# SCH_Plantcare_Module-v3_2024-10-30.net
KiCad netlist of a schematic drawn in EasyEDA
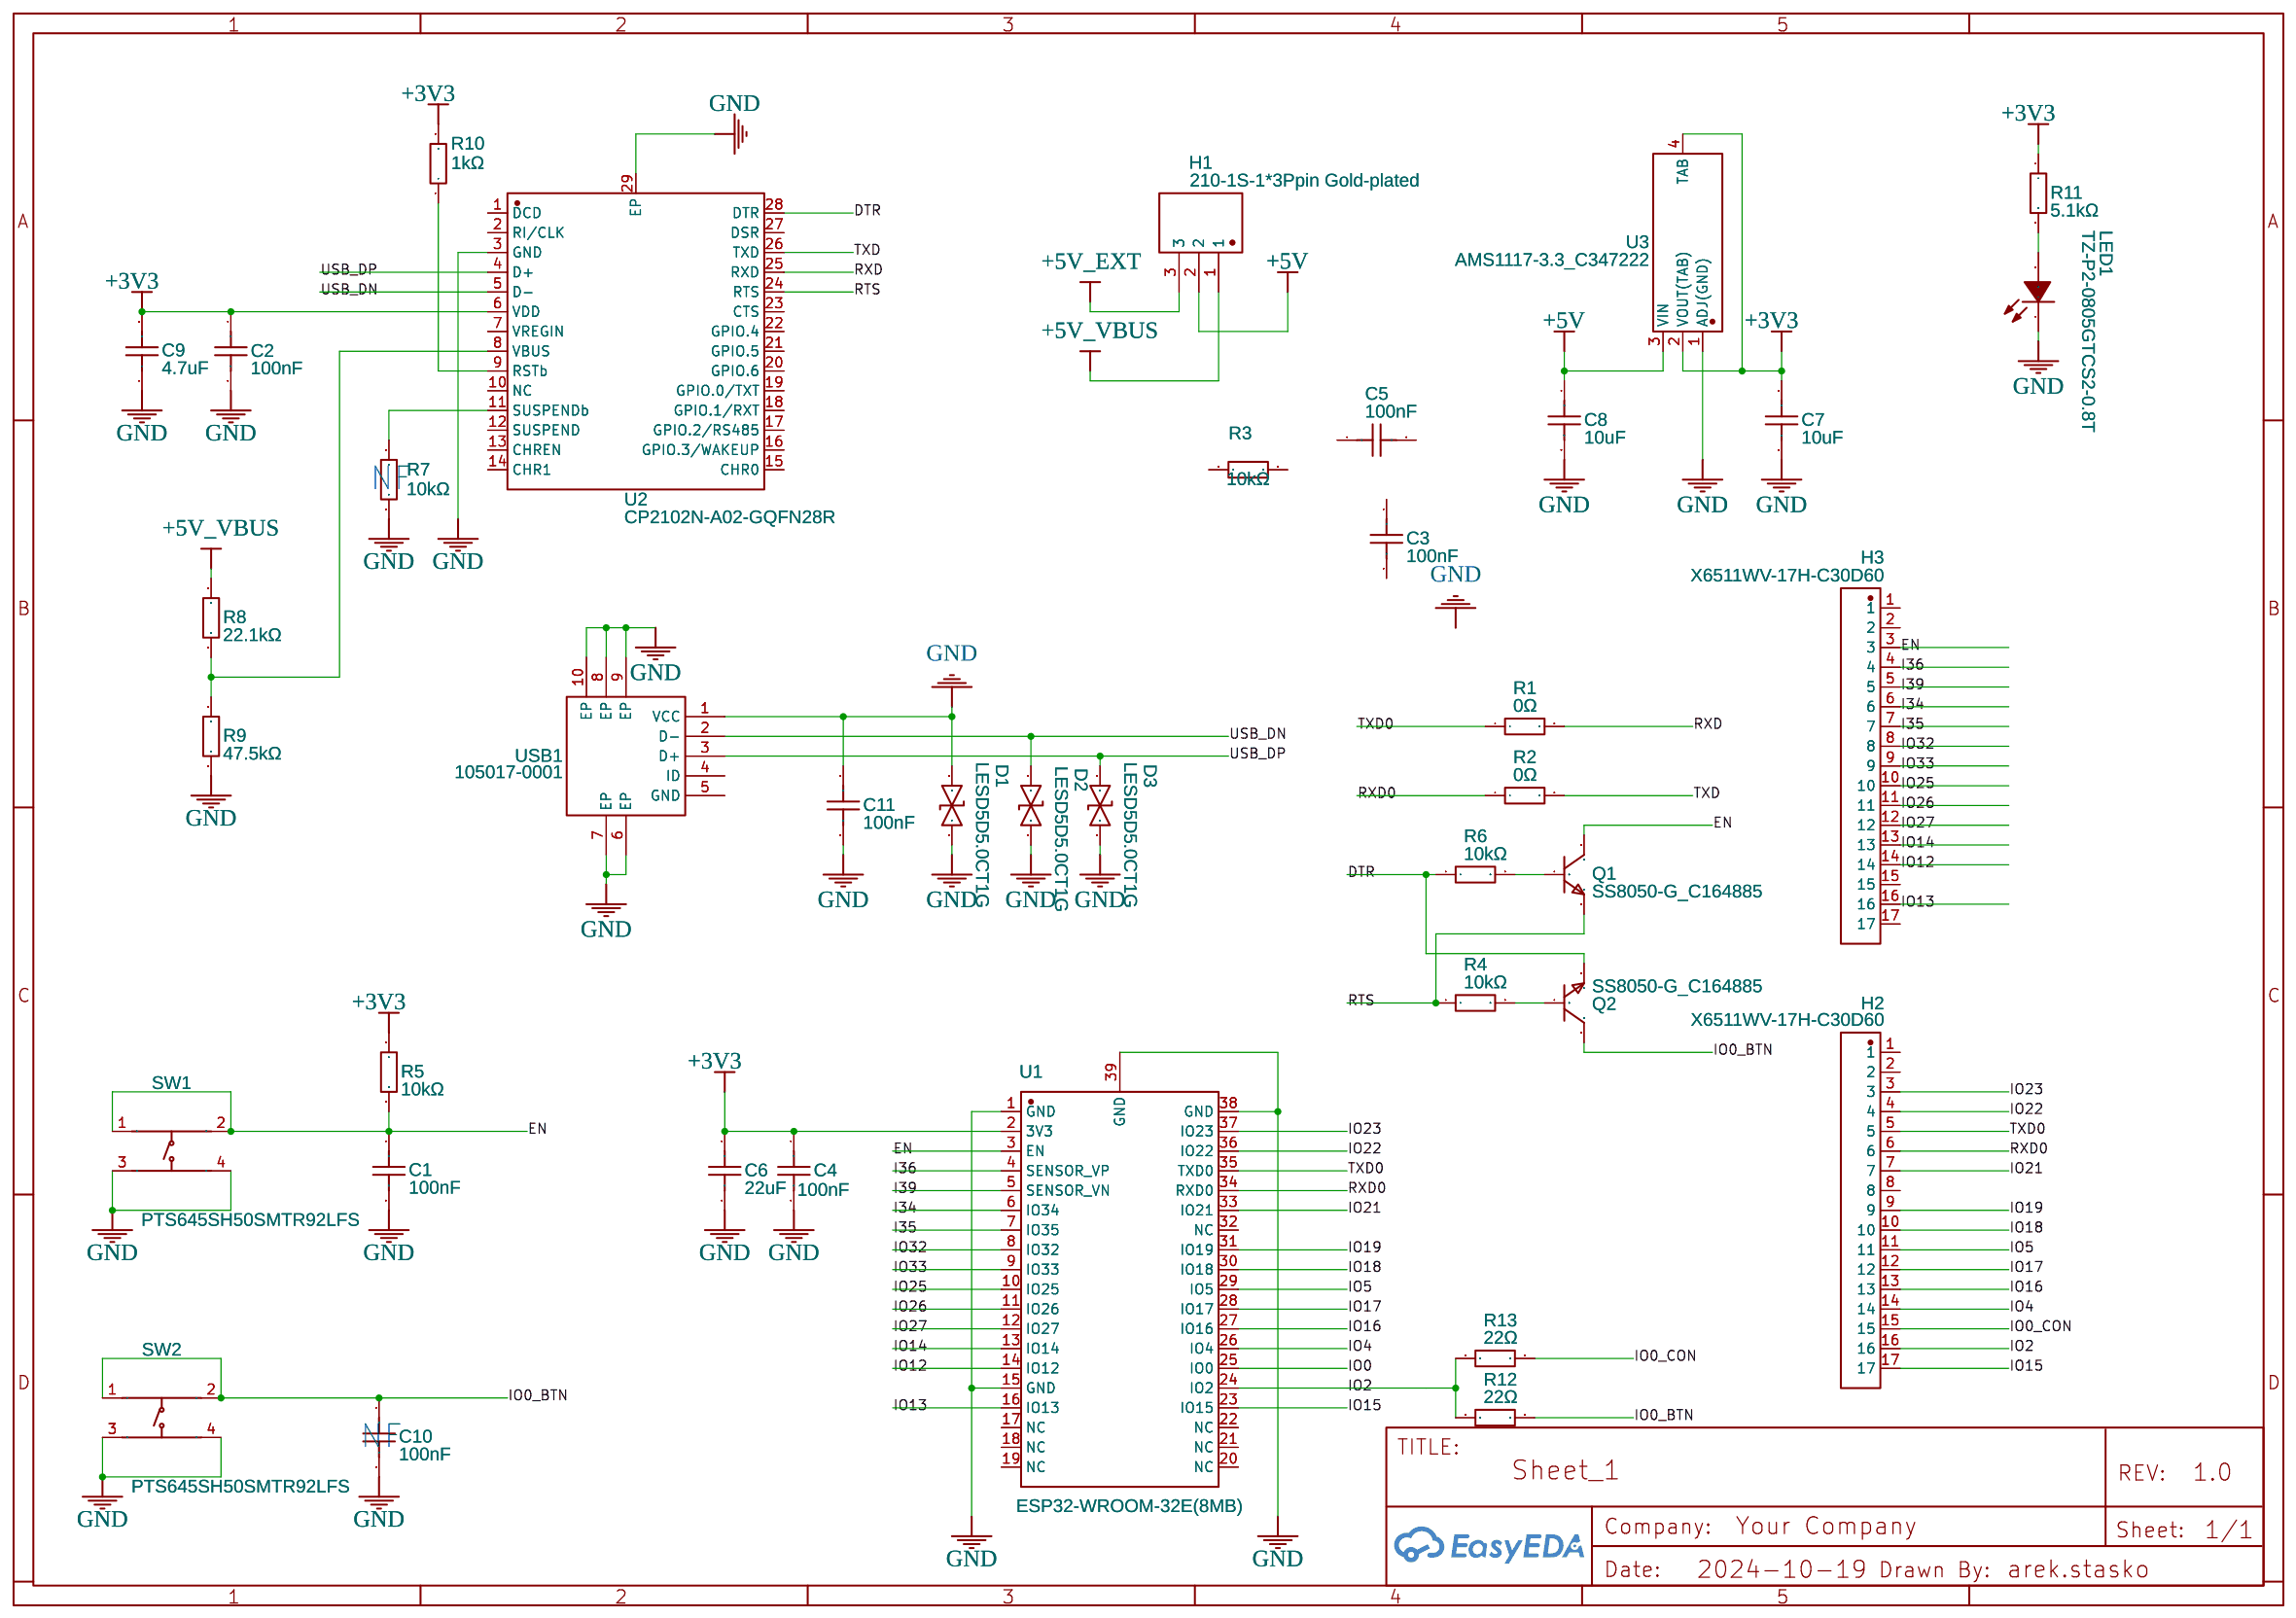
[diagram p0: schematic sheet]

(export (version "E")
  (design (tool "Eeschema 10.0.6"))
  (components
    (comp (ref "C1")
      (value "100nF")
      (fields
        (field (name "Manufacturer Part") "CL05B104KO5NNNC")
        (field (name "Manufacturer") "SAMSUNG(三星)")
      )
      (libsource (lib "") (part "CL05B104KO5NNNC_1"))
    )
    (comp (ref "C2")
      (value "100nF")
      (fields
        (field (name "Manufacturer Part") "CL05B104KO5NNNC")
        (field (name "Manufacturer") "SAMSUNG(三星)")
      )
      (libsource (lib "") (part "CL05B104KO5NNNC_1"))
    )
    (comp (ref "C3")
      (value "100nF")
      (fields
        (field (name "Manufacturer Part") "CL05B104KO5NNNC")
        (field (name "Manufacturer") "SAMSUNG(三星)")
      )
      (libsource (lib "") (part "CL05B104KO5NNNC_1"))
    )
    (comp (ref "C4")
      (value "100nF")
      (fields
        (field (name "Manufacturer Part") "CL05B104KO5NNNC")
        (field (name "Manufacturer") "SAMSUNG(三星)")
      )
      (libsource (lib "") (part "CL05B104KO5NNNC_1"))
    )
    (comp (ref "C5")
      (value "100nF")
      (fields
        (field (name "Manufacturer Part") "CL05B104KO5NNNC")
        (field (name "Manufacturer") "SAMSUNG(三星)")
      )
      (libsource (lib "") (part "CL05B104KO5NNNC"))
    )
    (comp (ref "C6")
      (value "22uF")
      (fields
        (field (name "Manufacturer Part") "CL21A226MAYNNNE")
        (field (name "Manufacturer") "SAMSUNG(三星)")
      )
      (libsource (lib "") (part "CL21A226MAYNNNE"))
    )
    (comp (ref "C7")
      (value "10uF")
      (fields
        (field (name "Manufacturer Part") "CL05A106MP5NUNC")
        (field (name "Manufacturer") "SAMSUNG(三星)")
      )
      (libsource (lib "") (part "CL05A106MP5NUNC_C315248"))
    )
    (comp (ref "C8")
      (value "10uF")
      (fields
        (field (name "Manufacturer Part") "CL05A106MP5NUNC")
        (field (name "Manufacturer") "SAMSUNG(三星)")
      )
      (libsource (lib "") (part "CL05A106MP5NUNC_C315248"))
    )
    (comp (ref "C9")
      (value "4.7uF")
      (fields
        (field (name "Manufacturer Part") "CL05A475KP5NRNC")
        (field (name "Manufacturer") "SAMSUNG(三星)")
      )
      (libsource (lib "") (part "CL05A475KP5NRNC"))
    )
    (comp (ref "C10")
      (value "100nF")
      (fields
        (field (name "Manufacturer Part") "CL05B104KO5NNNC")
        (field (name "Manufacturer") "SAMSUNG(三星)")
      )
      (libsource (lib "") (part "CL05B104KO5NNNC_1"))
    )
    (comp (ref "C11")
      (value "100nF")
      (fields
        (field (name "Manufacturer Part") "CL05B104KO5NNNC")
        (field (name "Manufacturer") "SAMSUNG(三星)")
      )
      (libsource (lib "") (part "CL05B104KO5NNNC_1"))
    )
    (comp (ref "D1")
      (value "LESD5D5.0CT1G")
      (fields (field (name "Manufacturer") "LRC(乐山无线电)"))
      (libsource (lib "") (part "LESD5D5.0CT1G_1"))
    )
    (comp (ref "D2")
      (value "LESD5D5.0CT1G")
      (fields (field (name "Manufacturer") "LRC(乐山无线电)"))
      (libsource (lib "") (part "LESD5D5.0CT1G"))
    )
    (comp (ref "D3")
      (value "LESD5D5.0CT1G")
      (fields (field (name "Manufacturer") "LRC(乐山无线电)"))
      (libsource (lib "") (part "LESD5D5.0CT1G"))
    )
    (comp (ref "H1")
      (value "210-1S-1*3Ppin Gold-plated")
      (fields (field (name "Manufacturer Part") "B-2101S03P-A110") (field (name "Manufacturer") "Ckmtw(灿科盟)"))
      (libsource (lib "") (part "210-1S-1*3Ppin Gold-plated"))
    )
    (comp (ref "H2")
      (value "X6511WV-17H-C30D60")
      (fields
        (field (name "Manufacturer Part") "X6511WV-17H-C60D30")
        (field (name "Manufacturer") "XKB Connection(中国星坤)")
      )
      (libsource (lib "") (part "X6511WV-17H-C30D60"))
    )
    (comp (ref "H3")
      (value "X6511WV-17H-C30D60")
      (fields
        (field (name "Manufacturer Part") "X6511WV-17H-C60D30")
        (field (name "Manufacturer") "XKB Connection(中国星坤)")
      )
      (libsource (lib "") (part "X6511WV-17H-C30D60"))
    )
    (comp (ref "LED1")
      (value "TZ-P2-0805GTCS2-0.8T")
      (fields (field (name "Manufacturer") "TUOZHAN(拓展光电)"))
      (libsource (lib "") (part "TZ-P2-0805GTCS2-0.8T"))
    )
    (comp (ref "Q1")
      (value "SS8050-G_C164885")
      (fields (field (name "Manufacturer Part") "SS8050-G") (field (name "Manufacturer") "CJ(江苏长电/长晶)"))
      (libsource (lib "") (part "SS8050-G_C164885"))
    )
    (comp (ref "Q2")
      (value "SS8050-G_C164885")
      (fields (field (name "Manufacturer Part") "SS8050-G") (field (name "Manufacturer") "CJ(江苏长电/长晶)"))
      (libsource (lib "") (part "SS8050-G_C164885_1"))
    )
    (comp (ref "R1")
      (value "0Ω")
      (fields
        (field (name "Manufacturer Part") "0402WGF0000TCE")
        (field (name "Manufacturer") "UNI-ROYAL(厚声)")
      )
      (libsource (lib "") (part "0402WGF0000TCE"))
    )
    (comp (ref "R2")
      (value "0Ω")
      (fields
        (field (name "Manufacturer Part") "0402WGF0000TCE")
        (field (name "Manufacturer") "UNI-ROYAL(厚声)")
      )
      (libsource (lib "") (part "0402WGF0000TCE"))
    )
    (comp (ref "R3")
      (value "10kΩ")
      (fields
        (field (name "Manufacturer Part") "0402WGF1002TCE")
        (field (name "Manufacturer") "UNI-ROYAL(厚声)")
      )
      (libsource (lib "") (part "0402WGF1002TCE_1"))
    )
    (comp (ref "R4")
      (value "10kΩ")
      (fields
        (field (name "Manufacturer Part") "0402WGF1002TCE")
        (field (name "Manufacturer") "UNI-ROYAL(厚声)")
      )
      (libsource (lib "") (part "0402WGF1002TCE_1"))
    )
    (comp (ref "R5")
      (value "10kΩ")
      (fields
        (field (name "Manufacturer Part") "0402WGF1002TCE")
        (field (name "Manufacturer") "UNI-ROYAL(厚声)")
      )
      (libsource (lib "") (part "0402WGF1002TCE"))
    )
    (comp (ref "R6")
      (value "10kΩ")
      (fields
        (field (name "Manufacturer Part") "0402WGF1002TCE")
        (field (name "Manufacturer") "UNI-ROYAL(厚声)")
      )
      (libsource (lib "") (part "0402WGF1002TCE_1"))
    )
    (comp (ref "R7")
      (value "10kΩ")
      (fields
        (field (name "Manufacturer Part") "0402WGF1002TCE")
        (field (name "Manufacturer") "UNI-ROYAL(厚声)")
      )
      (libsource (lib "") (part "0402WGF1002TCE"))
    )
    (comp (ref "R8")
      (value "22.1kΩ")
      (fields
        (field (name "Manufacturer Part") "0402WGF2212TCE")
        (field (name "Manufacturer") "UNI-ROYAL(厚声)")
      )
      (libsource (lib "") (part "0402WGF2212TCE"))
    )
    (comp (ref "R9")
      (value "47.5kΩ")
      (fields
        (field (name "Manufacturer Part") "0402WGF4752TCE")
        (field (name "Manufacturer") "UNI-ROYAL(厚声)")
      )
      (libsource (lib "") (part "0402WGF4752TCE"))
    )
    (comp (ref "R10")
      (value "1kΩ")
      (fields
        (field (name "Manufacturer Part") "0402WGF1001TCE")
        (field (name "Manufacturer") "UNI-ROYAL(厚声)")
      )
      (libsource (lib "") (part "0402WGF1001TCE"))
    )
    (comp (ref "R11")
      (value "5.1kΩ")
      (fields
        (field (name "Manufacturer Part") "0402WGF5101TCE")
        (field (name "Manufacturer") "UNI-ROYAL(厚声)")
      )
      (libsource (lib "") (part "0402WGF5101TCE"))
    )
    (comp (ref "R12")
      (value "22Ω")
      (fields
        (field (name "Manufacturer Part") "0402WGF220JTCE")
        (field (name "Manufacturer") "UNI-ROYAL(厚声)")
      )
      (libsource (lib "") (part "0402WGF220JTCE"))
    )
    (comp (ref "R13")
      (value "22Ω")
      (fields
        (field (name "Manufacturer Part") "0402WGF220JTCE")
        (field (name "Manufacturer") "UNI-ROYAL(厚声)")
      )
      (libsource (lib "") (part "0402WGF220JTCE"))
    )
    (comp (ref "SW1")
      (value "PTS645SH50SMTR92LFS")
      (fields (field (name "Manufacturer") "C&K"))
      (libsource (lib "") (part "PTS645SH50SMTR92LFS"))
    )
    (comp (ref "SW2")
      (value "PTS645SH50SMTR92LFS")
      (fields (field (name "Manufacturer") "C&K"))
      (libsource (lib "") (part "PTS645SH50SMTR92LFS"))
    )
    (comp (ref "U1")
      (value "ESP32-WROOM-32E(8MB)")
      (fields
        (field (name "Manufacturer Part") "ESP32-WROOM-32E-N8")
        (field (name "Manufacturer") "ESPRESSIF(乐鑫)")
      )
      (libsource (lib "") (part "ESP32-WROOM-32E(8MB)"))
    )
    (comp (ref "U2")
      (value "CP2102N-A02-GQFN28R")
      (fields (field (name "Manufacturer") "SKYWORKS/SILICON LABS(芯科)"))
      (libsource (lib "") (part "CP2102N-A02-GQFN28R"))
    )
    (comp (ref "U3")
      (value "AMS1117-3.3_C347222")
      (fields (field (name "Manufacturer Part") "AMS1117-3.3") (field (name "Manufacturer") "UMW(友台半导体)"))
      (libsource (lib "") (part "AMS1117-3.3_C347222"))
    )
    (comp (ref "USB1")
      (value "105017-0001")
      (fields (field (name "Manufacturer Part") "1050170001") (field (name "Manufacturer") "MOLEX"))
      (libsource (lib "") (part "105017-0001"))
    )
  )
  (nets
    (net (code "1") (name "+3V3") (class "Default")
      (node (ref "C2") (pin "1") (pinfunction "1_1") (pintype "unspecified"))
      (node (ref "C4") (pin "1") (pinfunction "1_1") (pintype "unspecified"))
      (node (ref "C6") (pin "1") (pinfunction "1_1") (pintype "unspecified"))
      (node (ref "C7") (pin "1") (pinfunction "1_1") (pintype "unspecified"))
      (node (ref "C9") (pin "2") (pinfunction "2_2") (pintype "unspecified"))
      (node (ref "R10") (pin "2") (pinfunction "2_2") (pintype "input"))
      (node (ref "R11") (pin "1") (pinfunction "1_1") (pintype "input"))
      (node (ref "R5") (pin "1") (pinfunction "1_1") (pintype "input"))
      (node (ref "U1") (pin "2") (pinfunction "3V3_2") (pintype "unspecified"))
      (node (ref "U2") (pin "6") (pinfunction "VDD_6") (pintype "unspecified"))
      (node (ref "U3") (pin "2") (pinfunction "VOUT(TAB)_2") (pintype "unspecified"))
      (node (ref "U3") (pin "4") (pinfunction "TAB_4") (pintype "unspecified"))
    )
    (net (code "2") (name "+5V") (class "Default")
      (node (ref "C8") (pin "1") (pinfunction "1_1") (pintype "unspecified"))
      (node (ref "H1") (pin "2") (pinfunction "2_2") (pintype "unspecified"))
      (node (ref "U3") (pin "3") (pinfunction "VIN_3") (pintype "unspecified"))
    )
    (net (code "3") (name "+5V_EXT") (class "Default")
      (node (ref "H1") (pin "3") (pinfunction "3_3") (pintype "unspecified"))
    )
    (net (code "4") (name "+5V_VBUS") (class "Default")
      (node (ref "H1") (pin "1") (pinfunction "1_1") (pintype "unspecified"))
      (node (ref "R8") (pin "1") (pinfunction "1_1") (pintype "input"))
    )
    (net (code "5") (name "/DTR") (class "Default")
      (node (ref "Q2") (pin "2") (pinfunction "E_2") (pintype "unspecified"))
      (node (ref "R6") (pin "1") (pinfunction "1_1") (pintype "input"))
      (node (ref "U2") (pin "28") (pinfunction "DTR_28") (pintype "unspecified"))
    )
    (net (code "6") (name "/EN") (class "Default")
      (node (ref "C1") (pin "1") (pinfunction "1_1") (pintype "unspecified"))
      (node (ref "H3") (pin "3") (pinfunction "3_3") (pintype "unspecified"))
      (node (ref "Q1") (pin "3") (pinfunction "C_3") (pintype "unspecified"))
      (node (ref "R5") (pin "2") (pinfunction "2_2") (pintype "input"))
      (node (ref "SW1") (pin "1") (pinfunction "1_1") (pintype "unspecified"))
      (node (ref "SW1") (pin "2") (pinfunction "2_2") (pintype "unspecified"))
      (node (ref "U1") (pin "3") (pinfunction "EN_3") (pintype "unspecified"))
    )
    (net (code "7") (name "/I34") (class "Default")
      (node (ref "H3") (pin "6") (pinfunction "6_6") (pintype "unspecified"))
      (node (ref "U1") (pin "6") (pinfunction "IO34_6") (pintype "unspecified"))
    )
    (net (code "8") (name "/I35") (class "Default")
      (node (ref "H3") (pin "7") (pinfunction "7_7") (pintype "unspecified"))
      (node (ref "U1") (pin "7") (pinfunction "IO35_7") (pintype "unspecified"))
    )
    (net (code "9") (name "/I36") (class "Default")
      (node (ref "H3") (pin "4") (pinfunction "4_4") (pintype "unspecified"))
      (node (ref "U1") (pin "4") (pinfunction "SENSOR_VP_4") (pintype "unspecified"))
    )
    (net (code "10") (name "/I39") (class "Default")
      (node (ref "H3") (pin "5") (pinfunction "5_5") (pintype "unspecified"))
      (node (ref "U1") (pin "5") (pinfunction "SENSOR_VN_5") (pintype "unspecified"))
    )
    (net (code "11") (name "/IO0") (class "Default")
      (node (ref "U1") (pin "25") (pinfunction "IO0_25") (pintype "unspecified"))
    )
    (net (code "12") (name "/IO0_BTN") (class "Default")
      (node (ref "C10") (pin "1") (pinfunction "1_1") (pintype "unspecified"))
      (node (ref "Q2") (pin "3") (pinfunction "C_3") (pintype "unspecified"))
      (node (ref "R12") (pin "2") (pinfunction "2_2") (pintype "input"))
      (node (ref "SW2") (pin "1") (pinfunction "1_1") (pintype "unspecified"))
      (node (ref "SW2") (pin "2") (pinfunction "2_2") (pintype "unspecified"))
    )
    (net (code "13") (name "/IO0_CON") (class "Default")
      (node (ref "H2") (pin "15") (pinfunction "15_15") (pintype "unspecified"))
      (node (ref "R13") (pin "2") (pinfunction "2_2") (pintype "input"))
    )
    (net (code "14") (name "/IO2") (class "Default")
      (node (ref "H2") (pin "16") (pinfunction "16_16") (pintype "unspecified"))
      (node (ref "R12") (pin "1") (pinfunction "1_1") (pintype "input"))
      (node (ref "R13") (pin "1") (pinfunction "1_1") (pintype "input"))
      (node (ref "U1") (pin "24") (pinfunction "IO2_24") (pintype "unspecified"))
    )
    (net (code "15") (name "/IO4") (class "Default")
      (node (ref "H2") (pin "14") (pinfunction "14_14") (pintype "unspecified"))
      (node (ref "U1") (pin "26") (pinfunction "IO4_26") (pintype "unspecified"))
    )
    (net (code "16") (name "/IO5") (class "Default")
      (node (ref "H2") (pin "11") (pinfunction "11_11") (pintype "unspecified"))
      (node (ref "U1") (pin "29") (pinfunction "IO5_29") (pintype "unspecified"))
    )
    (net (code "17") (name "/IO12") (class "Default")
      (node (ref "H3") (pin "14") (pinfunction "14_14") (pintype "unspecified"))
      (node (ref "U1") (pin "14") (pinfunction "IO12_14") (pintype "unspecified"))
    )
    (net (code "18") (name "/IO13") (class "Default")
      (node (ref "H3") (pin "16") (pinfunction "16_16") (pintype "unspecified"))
      (node (ref "U1") (pin "16") (pinfunction "IO13_16") (pintype "unspecified"))
    )
    (net (code "19") (name "/IO14") (class "Default")
      (node (ref "H3") (pin "13") (pinfunction "13_13") (pintype "unspecified"))
      (node (ref "U1") (pin "13") (pinfunction "IO14_13") (pintype "unspecified"))
    )
    (net (code "20") (name "/IO15") (class "Default")
      (node (ref "H2") (pin "17") (pinfunction "17_17") (pintype "unspecified"))
      (node (ref "U1") (pin "23") (pinfunction "IO15_23") (pintype "unspecified"))
    )
    (net (code "21") (name "/IO16") (class "Default")
      (node (ref "H2") (pin "13") (pinfunction "13_13") (pintype "unspecified"))
      (node (ref "U1") (pin "27") (pinfunction "IO16_27") (pintype "unspecified"))
    )
    (net (code "22") (name "/IO17") (class "Default")
      (node (ref "H2") (pin "12") (pinfunction "12_12") (pintype "unspecified"))
      (node (ref "U1") (pin "28") (pinfunction "IO17_28") (pintype "unspecified"))
    )
    (net (code "23") (name "/IO18") (class "Default")
      (node (ref "H2") (pin "10") (pinfunction "10_10") (pintype "unspecified"))
      (node (ref "U1") (pin "30") (pinfunction "IO18_30") (pintype "unspecified"))
    )
    (net (code "24") (name "/IO19") (class "Default")
      (node (ref "H2") (pin "9") (pinfunction "9_9") (pintype "unspecified"))
      (node (ref "U1") (pin "31") (pinfunction "IO19_31") (pintype "unspecified"))
    )
    (net (code "25") (name "/IO21") (class "Default")
      (node (ref "H2") (pin "7") (pinfunction "7_7") (pintype "unspecified"))
      (node (ref "U1") (pin "33") (pinfunction "IO21_33") (pintype "unspecified"))
    )
    (net (code "26") (name "/IO22") (class "Default")
      (node (ref "H2") (pin "4") (pinfunction "4_4") (pintype "unspecified"))
      (node (ref "U1") (pin "36") (pinfunction "IO22_36") (pintype "unspecified"))
    )
    (net (code "27") (name "/IO23") (class "Default")
      (node (ref "H2") (pin "3") (pinfunction "3_3") (pintype "unspecified"))
      (node (ref "U1") (pin "37") (pinfunction "IO23_37") (pintype "unspecified"))
    )
    (net (code "28") (name "/IO25") (class "Default")
      (node (ref "H3") (pin "10") (pinfunction "10_10") (pintype "unspecified"))
      (node (ref "U1") (pin "10") (pinfunction "IO25_10") (pintype "unspecified"))
    )
    (net (code "29") (name "/IO26") (class "Default")
      (node (ref "H3") (pin "11") (pinfunction "11_11") (pintype "unspecified"))
      (node (ref "U1") (pin "11") (pinfunction "IO26_11") (pintype "unspecified"))
    )
    (net (code "30") (name "/IO27") (class "Default")
      (node (ref "H3") (pin "12") (pinfunction "12_12") (pintype "unspecified"))
      (node (ref "U1") (pin "12") (pinfunction "IO27_12") (pintype "unspecified"))
    )
    (net (code "31") (name "/IO32") (class "Default")
      (node (ref "H3") (pin "8") (pinfunction "8_8") (pintype "unspecified"))
      (node (ref "U1") (pin "8") (pinfunction "IO32_8") (pintype "unspecified"))
    )
    (net (code "32") (name "/IO33") (class "Default")
      (node (ref "H3") (pin "9") (pinfunction "9_9") (pintype "unspecified"))
      (node (ref "U1") (pin "9") (pinfunction "IO33_9") (pintype "unspecified"))
    )
    (net (code "33") (name "/RTS") (class "Default")
      (node (ref "Q1") (pin "2") (pinfunction "E_2") (pintype "unspecified"))
      (node (ref "R4") (pin "1") (pinfunction "1_1") (pintype "input"))
      (node (ref "U2") (pin "24") (pinfunction "RTS_24") (pintype "unspecified"))
    )
    (net (code "34") (name "/RXD") (class "Default")
      (node (ref "R1") (pin "2") (pinfunction "2_2") (pintype "input"))
      (node (ref "U2") (pin "25") (pinfunction "RXD_25") (pintype "unspecified"))
    )
    (net (code "35") (name "/RXD0") (class "Default")
      (node (ref "H2") (pin "6") (pinfunction "6_6") (pintype "unspecified"))
      (node (ref "R2") (pin "1") (pinfunction "1_1") (pintype "input"))
      (node (ref "U1") (pin "34") (pinfunction "RXD0_34") (pintype "unspecified"))
    )
    (net (code "36") (name "/TXD") (class "Default")
      (node (ref "R2") (pin "2") (pinfunction "2_2") (pintype "input"))
      (node (ref "U2") (pin "26") (pinfunction "TXD_26") (pintype "unspecified"))
    )
    (net (code "37") (name "/TXD0") (class "Default")
      (node (ref "H2") (pin "5") (pinfunction "5_5") (pintype "unspecified"))
      (node (ref "R1") (pin "1") (pinfunction "1_1") (pintype "input"))
      (node (ref "U1") (pin "35") (pinfunction "TXD0_35") (pintype "unspecified"))
    )
    (net (code "38") (name "/USB_DN") (class "Default")
      (node (ref "D2") (pin "1") (pinfunction "1_1") (pintype "unspecified"))
      (node (ref "U2") (pin "5") (pinfunction "D-_5") (pintype "unspecified"))
      (node (ref "USB1") (pin "2") (pinfunction "D-_2") (pintype "unspecified"))
    )
    (net (code "39") (name "/USB_DP") (class "Default")
      (node (ref "D3") (pin "1") (pinfunction "1_1") (pintype "unspecified"))
      (node (ref "U2") (pin "4") (pinfunction "D+_4") (pintype "unspecified"))
      (node (ref "USB1") (pin "3") (pinfunction "D+_3") (pintype "unspecified"))
    )
    (net (code "40") (name "GND") (class "Default")
      (node (ref "C1") (pin "2") (pinfunction "2_2") (pintype "unspecified"))
      (node (ref "C10") (pin "2") (pinfunction "2_2") (pintype "unspecified"))
      (node (ref "C11") (pin "1") (pinfunction "1_1") (pintype "unspecified"))
      (node (ref "C11") (pin "2") (pinfunction "2_2") (pintype "unspecified"))
      (node (ref "C2") (pin "2") (pinfunction "2_2") (pintype "unspecified"))
      (node (ref "C4") (pin "2") (pinfunction "2_2") (pintype "unspecified"))
      (node (ref "C6") (pin "2") (pinfunction "2_2") (pintype "unspecified"))
      (node (ref "C7") (pin "2") (pinfunction "2_2") (pintype "unspecified"))
      (node (ref "C8") (pin "2") (pinfunction "2_2") (pintype "unspecified"))
      (node (ref "C9") (pin "1") (pinfunction "1_1") (pintype "unspecified"))
      (node (ref "D1") (pin "1") (pinfunction "1_1") (pintype "unspecified"))
      (node (ref "D1") (pin "2") (pinfunction "2_2") (pintype "unspecified"))
      (node (ref "D2") (pin "2") (pinfunction "2_2") (pintype "unspecified"))
      (node (ref "D3") (pin "2") (pinfunction "2_2") (pintype "unspecified"))
      (node (ref "LED1") (pin "1") (pinfunction "-_1") (pintype "unspecified"))
      (node (ref "R7") (pin "2") (pinfunction "2_2") (pintype "input"))
      (node (ref "R9") (pin "2") (pinfunction "2_2") (pintype "input"))
      (node (ref "SW1") (pin "3") (pinfunction "3_3") (pintype "unspecified"))
      (node (ref "SW1") (pin "4") (pinfunction "4_4") (pintype "unspecified"))
      (node (ref "SW2") (pin "3") (pinfunction "3_3") (pintype "unspecified"))
      (node (ref "SW2") (pin "4") (pinfunction "4_4") (pintype "unspecified"))
      (node (ref "U1") (pin "1") (pinfunction "GND_1") (pintype "unspecified"))
      (node (ref "U1") (pin "15") (pinfunction "GND_15") (pintype "unspecified"))
      (node (ref "U1") (pin "38") (pinfunction "GND_38") (pintype "unspecified"))
      (node (ref "U1") (pin "39") (pinfunction "GND_39") (pintype "unspecified"))
      (node (ref "U2") (pin "29") (pinfunction "EP_29") (pintype "unspecified"))
      (node (ref "U2") (pin "3") (pinfunction "GND_3") (pintype "unspecified"))
      (node (ref "U3") (pin "1") (pinfunction "ADJ(GND)_1") (pintype "unspecified"))
      (node (ref "USB1") (pin "1") (pinfunction "VCC_1") (pintype "unspecified"))
      (node (ref "USB1") (pin "10") (pinfunction "EP_10") (pintype "unspecified"))
      (node (ref "USB1") (pin "6") (pinfunction "EP_6") (pintype "unspecified"))
      (node (ref "USB1") (pin "7") (pinfunction "EP_7") (pintype "unspecified"))
      (node (ref "USB1") (pin "8") (pinfunction "EP_8") (pintype "unspecified"))
      (node (ref "USB1") (pin "9") (pinfunction "EP_9") (pintype "unspecified"))
    )
    (net (code "41") (name "Net-(LED1-+)") (class "Default")
      (node (ref "LED1") (pin "2") (pinfunction "+_2") (pintype "unspecified"))
      (node (ref "R11") (pin "2") (pinfunction "2_2") (pintype "input"))
    )
    (net (code "42") (name "Net-(Q1-B)") (class "Default")
      (node (ref "Q1") (pin "1") (pinfunction "B_1") (pintype "unspecified"))
      (node (ref "R6") (pin "2") (pinfunction "2_2") (pintype "input"))
    )
    (net (code "43") (name "Net-(Q2-B)") (class "Default")
      (node (ref "Q2") (pin "1") (pinfunction "B_1") (pintype "unspecified"))
      (node (ref "R4") (pin "2") (pinfunction "2_2") (pintype "input"))
    )
    (net (code "44") (name "Net-(U2-RSTb)") (class "Default")
      (node (ref "R10") (pin "1") (pinfunction "1_1") (pintype "input"))
      (node (ref "U2") (pin "9") (pinfunction "RSTb_9") (pintype "unspecified"))
    )
    (net (code "45") (name "Net-(U2-SUSPENDb)") (class "Default")
      (node (ref "R7") (pin "1") (pinfunction "1_1") (pintype "input"))
      (node (ref "U2") (pin "11") (pinfunction "SUSPENDb_11") (pintype "unspecified"))
    )
    (net (code "46") (name "Net-(U2-VBUS)") (class "Default")
      (node (ref "R8") (pin "2") (pinfunction "2_2") (pintype "input"))
      (node (ref "R9") (pin "1") (pinfunction "1_1") (pintype "input"))
      (node (ref "U2") (pin "8") (pinfunction "VBUS_8") (pintype "unspecified"))
    )
    (net (code "47") (name "unconnected-(C3-Pad1)") (class "Default")
      (node (ref "C3") (pin "1") (pinfunction "1_1") (pintype "unspecified"))
    )
    (net (code "48") (name "unconnected-(C3-Pad2)") (class "Default")
      (node (ref "C3") (pin "2") (pinfunction "2_2") (pintype "unspecified"))
    )
    (net (code "49") (name "unconnected-(C5-Pad1)") (class "Default")
      (node (ref "C5") (pin "1") (pinfunction "1_1") (pintype "unspecified"))
    )
    (net (code "50") (name "unconnected-(C5-Pad2)") (class "Default")
      (node (ref "C5") (pin "2") (pinfunction "2_2") (pintype "unspecified"))
    )
    (net (code "51") (name "unconnected-(H2-Pad1)") (class "Default")
      (node (ref "H2") (pin "1") (pinfunction "1_1") (pintype "unspecified"))
    )
    (net (code "52") (name "unconnected-(H2-Pad2)") (class "Default")
      (node (ref "H2") (pin "2") (pinfunction "2_2") (pintype "unspecified"))
    )
    (net (code "53") (name "unconnected-(H2-Pad8)") (class "Default")
      (node (ref "H2") (pin "8") (pinfunction "8_8") (pintype "unspecified"))
    )
    (net (code "54") (name "unconnected-(H3-Pad1)") (class "Default")
      (node (ref "H3") (pin "1") (pinfunction "1_1") (pintype "unspecified"))
    )
    (net (code "55") (name "unconnected-(H3-Pad2)") (class "Default")
      (node (ref "H3") (pin "2") (pinfunction "2_2") (pintype "unspecified"))
    )
    (net (code "56") (name "unconnected-(H3-Pad15)") (class "Default")
      (node (ref "H3") (pin "15") (pinfunction "15_15") (pintype "unspecified"))
    )
    (net (code "57") (name "unconnected-(H3-Pad17)") (class "Default")
      (node (ref "H3") (pin "17") (pinfunction "17_17") (pintype "unspecified"))
    )
    (net (code "58") (name "unconnected-(R3-Pad1)") (class "Default")
      (node (ref "R3") (pin "1") (pinfunction "1_1") (pintype "input"))
    )
    (net (code "59") (name "unconnected-(R3-Pad2)") (class "Default")
      (node (ref "R3") (pin "2") (pinfunction "2_2") (pintype "input"))
    )
    (net (code "60") (name "unconnected-(U1-NC-Pad17)") (class "Default")
      (node (ref "U1") (pin "17") (pinfunction "NC_17") (pintype "unspecified"))
    )
    (net (code "61") (name "unconnected-(U1-NC-Pad18)") (class "Default")
      (node (ref "U1") (pin "18") (pinfunction "NC_18") (pintype "unspecified"))
    )
    (net (code "62") (name "unconnected-(U1-NC-Pad19)") (class "Default")
      (node (ref "U1") (pin "19") (pinfunction "NC_19") (pintype "unspecified"))
    )
    (net (code "63") (name "unconnected-(U1-NC-Pad20)") (class "Default")
      (node (ref "U1") (pin "20") (pinfunction "NC_20") (pintype "unspecified"))
    )
    (net (code "64") (name "unconnected-(U1-NC-Pad21)") (class "Default")
      (node (ref "U1") (pin "21") (pinfunction "NC_21") (pintype "unspecified"))
    )
    (net (code "65") (name "unconnected-(U1-NC-Pad22)") (class "Default")
      (node (ref "U1") (pin "22") (pinfunction "NC_22") (pintype "unspecified"))
    )
    (net (code "66") (name "unconnected-(U1-NC-Pad32)") (class "Default")
      (node (ref "U1") (pin "32") (pinfunction "NC_32") (pintype "unspecified"))
    )
    (net (code "67") (name "unconnected-(U2-CHR0-Pad15)") (class "Default")
      (node (ref "U2") (pin "15") (pinfunction "CHR0_15") (pintype "unspecified"))
    )
    (net (code "68") (name "unconnected-(U2-CHR1-Pad14)") (class "Default")
      (node (ref "U2") (pin "14") (pinfunction "CHR1_14") (pintype "unspecified"))
    )
    (net (code "69") (name "unconnected-(U2-CHREN-Pad13)") (class "Default")
      (node (ref "U2") (pin "13") (pinfunction "CHREN_13") (pintype "unspecified"))
    )
    (net (code "70") (name "unconnected-(U2-CTS-Pad23)") (class "Default")
      (node (ref "U2") (pin "23") (pinfunction "CTS_23") (pintype "unspecified"))
    )
    (net (code "71") (name "unconnected-(U2-DCD-Pad1)") (class "Default")
      (node (ref "U2") (pin "1") (pinfunction "DCD_1") (pintype "unspecified"))
    )
    (net (code "72") (name "unconnected-(U2-DSR-Pad27)") (class "Default")
      (node (ref "U2") (pin "27") (pinfunction "DSR_27") (pintype "unspecified"))
    )
    (net (code "73") (name "unconnected-(U2-GPIO.0{slash}TXT-Pad19)") (class "Default")
      (node (ref "U2") (pin "19") (pinfunction "GPIO.0/TXT_19") (pintype "unspecified"))
    )
    (net (code "74") (name "unconnected-(U2-GPIO.1{slash}RXT-Pad18)") (class "Default")
      (node (ref "U2") (pin "18") (pinfunction "GPIO.1/RXT_18") (pintype "unspecified"))
    )
    (net (code "75") (name "unconnected-(U2-GPIO.2{slash}RS485-Pad17)") (class "Default")
      (node (ref "U2") (pin "17") (pinfunction "GPIO.2/RS485_17") (pintype "unspecified"))
    )
    (net (code "76") (name "unconnected-(U2-GPIO.3{slash}WAKEUP-Pad16)") (class "Default")
      (node (ref "U2") (pin "16") (pinfunction "GPIO.3/WAKEUP_16") (pintype "unspecified"))
    )
    (net (code "77") (name "unconnected-(U2-GPIO.4-Pad22)") (class "Default")
      (node (ref "U2") (pin "22") (pinfunction "GPIO.4_22") (pintype "unspecified"))
    )
    (net (code "78") (name "unconnected-(U2-GPIO.5-Pad21)") (class "Default")
      (node (ref "U2") (pin "21") (pinfunction "GPIO.5_21") (pintype "unspecified"))
    )
    (net (code "79") (name "unconnected-(U2-GPIO.6-Pad20)") (class "Default")
      (node (ref "U2") (pin "20") (pinfunction "GPIO.6_20") (pintype "unspecified"))
    )
    (net (code "80") (name "unconnected-(U2-NC-Pad10)") (class "Default")
      (node (ref "U2") (pin "10") (pinfunction "NC_10") (pintype "unspecified"))
    )
    (net (code "81") (name "unconnected-(U2-RI{slash}CLK-Pad2)") (class "Default")
      (node (ref "U2") (pin "2") (pinfunction "RI/CLK_2") (pintype "unspecified"))
    )
    (net (code "82") (name "unconnected-(U2-SUSPEND-Pad12)") (class "Default")
      (node (ref "U2") (pin "12") (pinfunction "SUSPEND_12") (pintype "unspecified"))
    )
    (net (code "83") (name "unconnected-(U2-VREGIN-Pad7)") (class "Default")
      (node (ref "U2") (pin "7") (pinfunction "VREGIN_7") (pintype "unspecified"))
    )
    (net (code "84") (name "unconnected-(USB1-GND-Pad5)") (class "Default")
      (node (ref "USB1") (pin "5") (pinfunction "GND_5") (pintype "unspecified"))
    )
    (net (code "85") (name "unconnected-(USB1-ID-Pad4)") (class "Default")
      (node (ref "USB1") (pin "4") (pinfunction "ID_4") (pintype "unspecified"))
    )
  )
)
